# Gate_Driver_3.net
KiCad netlist of a schematic drawn in Altium Designer
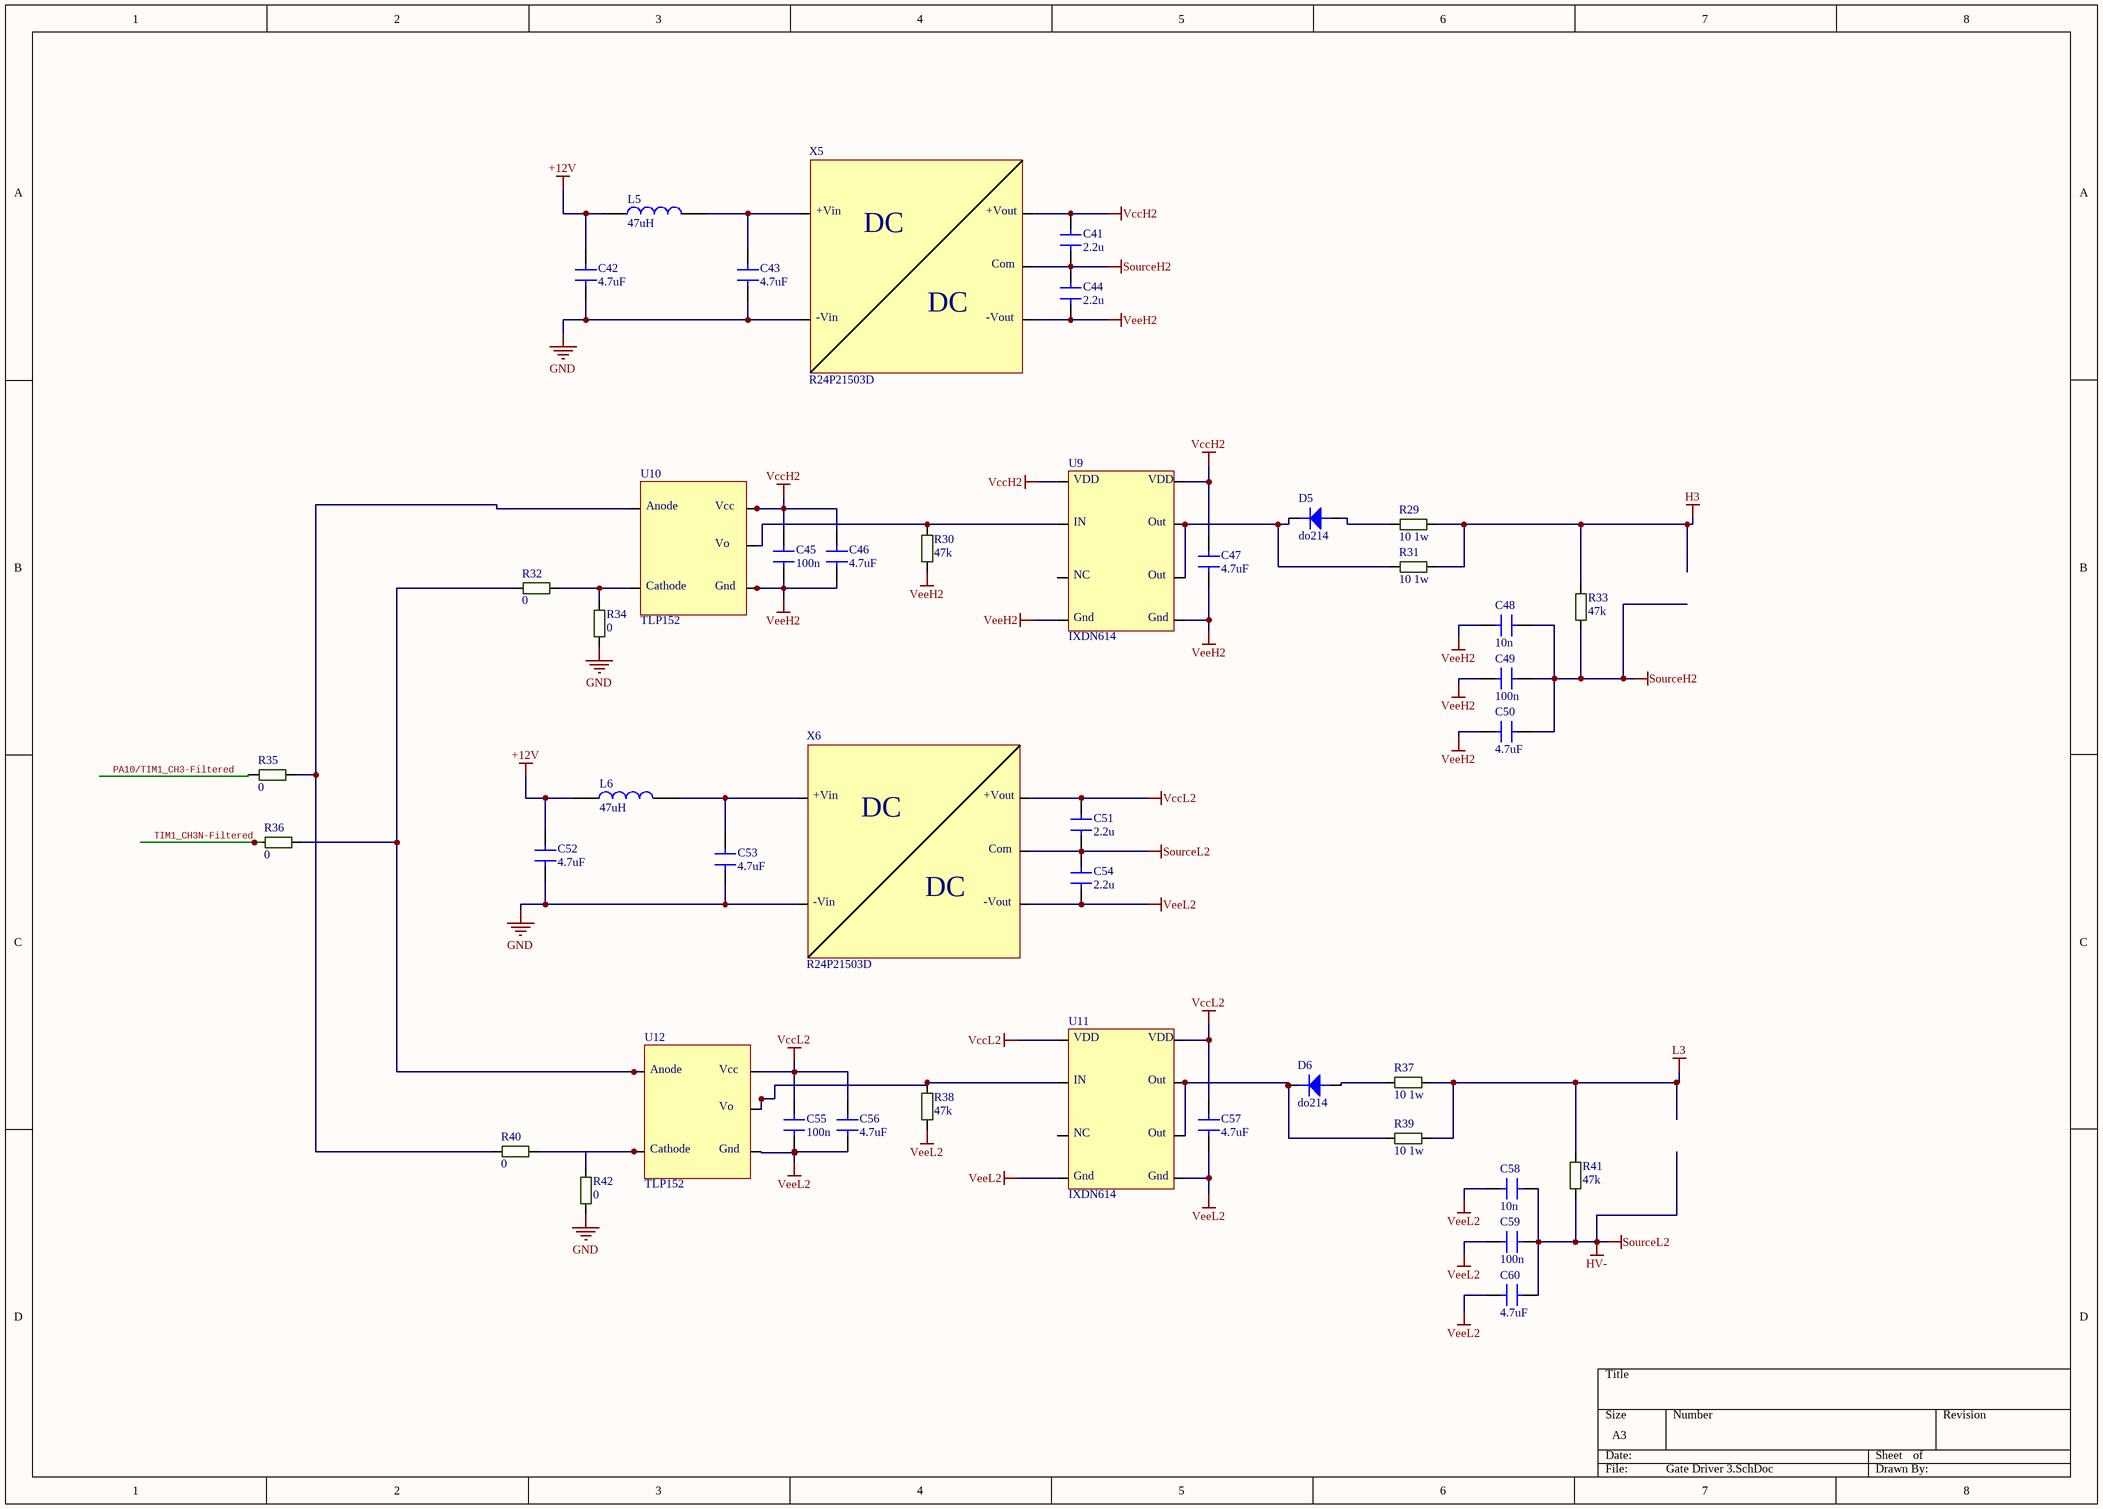
[diagram p0: Gate Driver 3.SchDoc]

(export (version "E")
  (design (tool "Eeschema 10.0.6"))
  (components
    (comp (ref "C41")
      (value "2.2u")
      (footprint "C-0805")
      (libsource (lib "Gate Driver Board") (part "C-0805"))
    )
    (comp (ref "C42")
      (value "4.7uF")
      (footprint "C-1206")
      (description "Cap1206 4.7uF")
      (fields (field (name "ÖZDISAN PART NUMBER") "CL31B475KBHNNNE") (field (name "MANUFACTURER") "SAMSUNG"))
      (libsource (lib "Gate Driver Board") (part "Cap1206"))
    )
    (comp (ref "C43")
      (value "4.7uF")
      (footprint "C-1206")
      (description "Cap1206 4.7uF")
      (fields (field (name "ÖZDISAN PART NUMBER") "CL31B475KBHNNNE") (field (name "MANUFACTURER") "SAMSUNG"))
      (libsource (lib "Gate Driver Board") (part "Cap1206"))
    )
    (comp (ref "C44")
      (value "2.2u")
      (footprint "C-0805")
      (libsource (lib "Gate Driver Board") (part "C-0805"))
    )
    (comp (ref "C45")
      (value "100n")
      (footprint "C-0805")
      (libsource (lib "Gate Driver Board") (part "C-0805"))
    )
    (comp (ref "C46")
      (value "4.7uF")
      (footprint "C-1206")
      (description "Cap1206 4.7uF")
      (libsource (lib "Gate Driver Board") (part "C-1206"))
    )
    (comp (ref "C47")
      (value "4.7uF")
      (footprint "C-1206")
      (description "Cap1206 4.7uF")
      (libsource (lib "Gate Driver Board") (part "C-1206"))
    )
    (comp (ref "C48")
      (value "10n")
      (footprint "C-0805")
      (libsource (lib "Gate Driver Board") (part "C-0805"))
    )
    (comp (ref "C49")
      (value "100n")
      (footprint "C-0805")
      (libsource (lib "Gate Driver Board") (part "C-0805"))
    )
    (comp (ref "C50")
      (value "4.7uF")
      (footprint "C-1206")
      (description "Cap1206 4.7uF")
      (fields (field (name "ÖZDISAN PART NUMBER") " CL31B475KBHNNNE") (field (name "MANUFACTURER") "SAMSUNG"))
      (libsource (lib "Gate Driver Board") (part "Cap1206"))
    )
    (comp (ref "C51")
      (value "2.2u")
      (footprint "C-0805")
      (libsource (lib "Gate Driver Board") (part "C-0805"))
    )
    (comp (ref "C52")
      (value "4.7uF")
      (footprint "C-1206")
      (description "Cap1206 4.7uF")
      (fields (field (name "ÖZDISAN PART NUMBER") "CL31B475KBHNNNE") (field (name "MANUFACTURER") "SAMSUNG"))
      (libsource (lib "Gate Driver Board") (part "Cap1206"))
    )
    (comp (ref "C53")
      (value "4.7uF")
      (footprint "C-1206")
      (description "Cap1206 4.7uF")
      (fields (field (name "ÖZDISAN PART NUMBER") " CL31B475KBHNNNE") (field (name "MANUFACTURER") "SAMSUNG"))
      (libsource (lib "Gate Driver Board") (part "Cap1206"))
    )
    (comp (ref "C54")
      (value "2.2u")
      (footprint "C-0805")
      (libsource (lib "Gate Driver Board") (part "C-0805"))
    )
    (comp (ref "C55")
      (value "100n")
      (footprint "C-0805")
      (libsource (lib "Gate Driver Board") (part "C-0805"))
    )
    (comp (ref "C56")
      (value "4.7uF")
      (footprint "C-1206")
      (description "Cap1206 4.7uF")
      (libsource (lib "Gate Driver Board") (part "C-1206"))
    )
    (comp (ref "C57")
      (value "4.7uF")
      (footprint "C-1206")
      (description "Cap1206 4.7uF")
      (libsource (lib "Gate Driver Board") (part "C-1206"))
    )
    (comp (ref "C58")
      (value "10n")
      (footprint "C-0805")
      (libsource (lib "Gate Driver Board") (part "C-0805"))
    )
    (comp (ref "C59")
      (value "100n")
      (footprint "C-0805")
      (libsource (lib "Gate Driver Board") (part "C-0805"))
    )
    (comp (ref "C60")
      (value "4.7uF")
      (footprint "C-1206")
      (description "Cap1206 4.7uF")
      (fields (field (name "ÖZDISAN PART NUMBER") "CL31B475KBHNNNE") (field (name "MANUFACTURER") "SAMSUNG"))
      (libsource (lib "Gate Driver Board") (part "Cap1206"))
    )
    (comp (ref "D5")
      (value "do214")
      (footprint "DO-214AC")
      (description "DIODE FAST SWITCHING Single 150mA 75V SMT SOD323")
      (libsource (lib "Gate Driver Board") (part "do214"))
    )
    (comp (ref "D6")
      (value "do214")
      (footprint "DO-214AC")
      (description "DIODE FAST SWITCHING Single 150mA 75V SMT SOD323")
      (libsource (lib "Gate Driver Board") (part "do214"))
    )
    (comp (ref "L5")
      (value "47uH")
      (footprint "WE-TPC_282892")
      (libsource (lib "Gate Driver Board") (part "inductor"))
    )
    (comp (ref "L6")
      (value "47uH")
      (footprint "WE-TPC_282892")
      (libsource (lib "Gate Driver Board") (part "inductor"))
    )
    (comp (ref "R29")
      (value "10 1w")
      (footprint "R-2512")
      (libsource (lib "Gate Driver Board") (part "R-2512"))
    )
    (comp (ref "R30")
      (value "47k")
      (footprint "R-0805")
      (description "RES.(2012) 0805 47K Ohms 5% 1/8W-S 100PPM")
      (fields (field (name "MANUFACTURER") "ROYALOHM") (field (name "ÖZDISAN PART NUMBER") "0805S8J0473T5E"))
      (libsource (lib "Gate Driver Board") (part "Res0805"))
    )
    (comp (ref "R31")
      (value "10 1w")
      (footprint "R-2512")
      (libsource (lib "Gate Driver Board") (part "R-2512"))
    )
    (comp (ref "R32")
      (value "0")
      (footprint "R-0805")
      (description "Res0805 0R")
      (fields (field (name "MANUFACTURER") "ROYALOHM") (field (name "ÖZDISAN PART NUMBER") "0805S8J0000T5E"))
      (libsource (lib "Gate Driver Board") (part "Res0805"))
    )
    (comp (ref "R33")
      (value "47k")
      (footprint "R-0805")
      (description "RES.(2012) 0805 47K Ohms 5% 1/8W-S 100PPM")
      (fields (field (name "ÖZDISAN PART NUMBER") "0805S8J0473T5E") (field (name "MANUFACTURER") "ROYALOHM"))
      (libsource (lib "Gate Driver Board") (part "Res0805"))
    )
    (comp (ref "R34")
      (value "0")
      (footprint "R-0805")
      (description "Res0805 0R")
      (fields (field (name "MANUFACTURER") "ROYALOHM") (field (name "ÖZDISAN PART NUMBER") "0805S8J0000T5E"))
      (libsource (lib "Gate Driver Board") (part "Res0805"))
    )
    (comp (ref "R35")
      (value "0")
      (footprint "R-0805")
      (description "Res0805 0R")
      (fields (field (name "MANUFACTURER") "ROYALOHM") (field (name "ÖZDISAN PART NUMBER") "0805S8J0000T5E"))
      (libsource (lib "Gate Driver Board") (part "Res0805"))
    )
    (comp (ref "R36")
      (value "0")
      (footprint "R-0805")
      (description "Res0805 0R")
      (fields (field (name "MANUFACTURER") "ROYALOHM") (field (name "ÖZDISAN PART NUMBER") "0805S8J0000T5E"))
      (libsource (lib "Gate Driver Board") (part "Res0805"))
    )
    (comp (ref "R37")
      (value "10 1w")
      (footprint "R-2512")
      (libsource (lib "Gate Driver Board") (part "R-2512"))
    )
    (comp (ref "R38")
      (value "47k")
      (footprint "R-0805")
      (description "RES.(2012) 0805 47K Ohms 5% 1/8W-S 100PPM")
      (fields (field (name "ÖZDISAN PART NUMBER") "0805S8J0473T5E") (field (name "MANUFACTURER") "ROYALOHM"))
      (libsource (lib "Gate Driver Board") (part "Res0805"))
    )
    (comp (ref "R39")
      (value "10 1w")
      (footprint "R-2512")
      (libsource (lib "Gate Driver Board") (part "R-2512"))
    )
    (comp (ref "R40")
      (value "0")
      (footprint "R-0805")
      (description "Res0805 0R")
      (fields (field (name "MANUFACTURER") "ROYALOHM") (field (name "ÖZDISAN PART NUMBER") "0805S8J0000T5E"))
      (libsource (lib "Gate Driver Board") (part "Res0805"))
    )
    (comp (ref "R41")
      (value "47k")
      (footprint "R-0805")
      (description "RES.(2012) 0805 47K Ohms 5% 1/8W-S 100PPM")
      (fields (field (name "ÖZDISAN PART NUMBER") "0805S8J0473T5E") (field (name "MANUFACTURER") "ROYALOHM"))
      (libsource (lib "Gate Driver Board") (part "Res0805"))
    )
    (comp (ref "R42")
      (value "0")
      (footprint "R-0805")
      (description "Res0805 0R")
      (fields (field (name "MANUFACTURER") "ROYALOHM") (field (name "ÖZDISAN PART NUMBER") "0805S8J0000T5E"))
      (libsource (lib "Gate Driver Board") (part "Res0805"))
    )
    (comp (ref "U9")
      (value "IXDN614")
      (footprint "FAN3122 Soic8")
      (description "14A 8SOIC EXP MTL NON INVERTING")
      (fields
        (field (name "MANUFACTURER") "Ixys Clare")
        (field (name "MANUFACTURER PART NUMBER") "IXDN614SITR")
      )
      (libsource (lib "Gate Driver Board") (part "IXDN614SITR"))
    )
    (comp (ref "U10")
      (value "TLP152")
      (footprint "TLP152")
      (description "OPTOISO 3.75KV GATE DRIVER 6SO-5")
      (fields
        (field (name "MANUFACTURER") "Toshiba")
        (field (name "MANUFACTURER PART NUMBER") "TLP152(TPL,E")
      )
      (libsource (lib "Gate Driver Board") (part "TLP152(TPL,E"))
    )
    (comp (ref "U11")
      (value "IXDN614")
      (footprint "FAN3122 Soic8")
      (description "14A 8SOIC EXP MTL NON INVERTING")
      (fields
        (field (name "MANUFACTURER") "Ixys Clare")
        (field (name "MANUFACTURER PART NUMBER") "IXDN614SITR")
      )
      (libsource (lib "Gate Driver Board") (part "IXDN614SITR"))
    )
    (comp (ref "U12")
      (value "TLP152")
      (footprint "TLP152")
      (description "OPTOISO 3.75KV GATE DRIVER 6SO-5")
      (fields
        (field (name "MANUFACTURER") "Toshiba")
        (field (name "MANUFACTURER PART NUMBER") "TLP152(TPL,E")
      )
      (libsource (lib "Gate Driver Board") (part "TLP152(TPL,E"))
    )
    (comp (ref "X5")
      (value "R24P21503D")
      (footprint "SIP7")
      (fields (field (name "MANUFACTURER") "Recom"))
      (libsource (lib "Gate Driver Board") (part "R24P21503D"))
    )
    (comp (ref "X6")
      (value "R24P21503D")
      (footprint "SIP7")
      (fields (field (name "MANUFACTURER") "Recom"))
      (libsource (lib "Gate Driver Board") (part "R24P21503D"))
    )
  )
  (nets
    (net (code "1") (name "+12V") (class "Default")
      (node (ref "C42") (pin "2") (pinfunction "2_2") (pintype "passive"))
      (node (ref "C52") (pin "2") (pinfunction "2_2") (pintype "passive"))
      (node (ref "L5") (pin "1") (pinfunction "1_1") (pintype "passive"))
      (node (ref "L6") (pin "1") (pinfunction "1_1") (pintype "passive"))
    )
    (net (code "2") (name "/PA10{slash}TIM1_CH3-Filtered") (class "Default")
      (node (ref "R35") (pin "1") (pinfunction "1_1") (pintype "passive"))
    )
    (net (code "3") (name "/TIM1_CH3N-Filtered") (class "Default")
      (node (ref "R36") (pin "1") (pinfunction "1_1") (pintype "passive"))
    )
    (net (code "4") (name "GND") (class "Default")
      (node (ref "C42") (pin "1") (pinfunction "1_1") (pintype "passive"))
      (node (ref "C43") (pin "1") (pinfunction "1_1") (pintype "passive"))
      (node (ref "C52") (pin "1") (pinfunction "1_1") (pintype "passive"))
      (node (ref "C53") (pin "1") (pinfunction "1_1") (pintype "passive"))
      (node (ref "R34") (pin "1") (pinfunction "1_1") (pintype "passive"))
      (node (ref "R42") (pin "1") (pinfunction "1_1") (pintype "passive"))
      (node (ref "X5") (pin "2") (pinfunction "2_2") (pintype "passive"))
      (node (ref "X6") (pin "2") (pinfunction "2_2") (pintype "passive"))
    )
    (net (code "5") (name "H3") (class "Default")
      (node (ref "R29") (pin "2") (pinfunction "2_2") (pintype "passive"))
      (node (ref "R31") (pin "2") (pinfunction "2_2") (pintype "passive"))
      (node (ref "R33") (pin "2") (pinfunction "2_2") (pintype "passive"))
    )
    (net (code "6") (name "HV-") (class "Default")
      (node (ref "C51") (pin "1") (pinfunction "1_1") (pintype "passive"))
      (node (ref "C54") (pin "2") (pinfunction "2_2") (pintype "passive"))
      (node (ref "C58") (pin "1") (pinfunction "1_1") (pintype "passive"))
      (node (ref "C59") (pin "1") (pinfunction "1_1") (pintype "passive"))
      (node (ref "C60") (pin "2") (pinfunction "2_2") (pintype "passive"))
      (node (ref "R41") (pin "1") (pinfunction "1_1") (pintype "passive"))
      (node (ref "X6") (pin "6") (pinfunction "6_6") (pintype "passive"))
    )
    (net (code "7") (name "L3") (class "Default")
      (node (ref "R37") (pin "2") (pinfunction "2_2") (pintype "passive"))
      (node (ref "R39") (pin "2") (pinfunction "2_2") (pintype "passive"))
      (node (ref "R41") (pin "2") (pinfunction "2_2") (pintype "passive"))
    )
    (net (code "8") (name "Net-(C43-Pad2)") (class "Default")
      (node (ref "C43") (pin "2") (pinfunction "2_2") (pintype "passive"))
      (node (ref "L5") (pin "2") (pinfunction "2_2") (pintype "passive"))
      (node (ref "X5") (pin "1") (pinfunction "1_1") (pintype "passive"))
    )
    (net (code "9") (name "Net-(C53-Pad2)") (class "Default")
      (node (ref "C53") (pin "2") (pinfunction "2_2") (pintype "passive"))
      (node (ref "L6") (pin "2") (pinfunction "2_2") (pintype "passive"))
      (node (ref "X6") (pin "1") (pinfunction "1_1") (pintype "passive"))
    )
    (net (code "10") (name "Net-(D5-Pada)") (class "Default")
      (node (ref "D5") (pin "a") (pinfunction "a_a") (pintype "passive"))
      (node (ref "R29") (pin "1") (pinfunction "1_1") (pintype "passive"))
    )
    (net (code "11") (name "Net-(D5-Padk)") (class "Default")
      (node (ref "D5") (pin "k") (pinfunction "k_k") (pintype "passive"))
      (node (ref "R31") (pin "1") (pinfunction "1_1") (pintype "passive"))
      (node (ref "U9") (pin "6") (pinfunction "6_6") (pintype "passive"))
      (node (ref "U9") (pin "7") (pinfunction "7_7") (pintype "passive"))
    )
    (net (code "12") (name "Net-(D6-Pada)") (class "Default")
      (node (ref "D6") (pin "a") (pinfunction "a_a") (pintype "passive"))
      (node (ref "R37") (pin "1") (pinfunction "1_1") (pintype "passive"))
    )
    (net (code "13") (name "Net-(D6-Padk)") (class "Default")
      (node (ref "D6") (pin "k") (pinfunction "k_k") (pintype "passive"))
      (node (ref "R39") (pin "1") (pinfunction "1_1") (pintype "passive"))
      (node (ref "U11") (pin "6") (pinfunction "6_6") (pintype "passive"))
      (node (ref "U11") (pin "7") (pinfunction "7_7") (pintype "passive"))
    )
    (net (code "14") (name "Net-(R30-Pad2)") (class "Default")
      (node (ref "R30") (pin "2") (pinfunction "2_2") (pintype "passive"))
      (node (ref "U10") (pin "4") (pinfunction "4_4") (pintype "passive"))
      (node (ref "U9") (pin "2") (pinfunction "2_2") (pintype "passive"))
    )
    (net (code "15") (name "Net-(R32-Pad1)") (class "Default")
      (node (ref "R32") (pin "1") (pinfunction "1_1") (pintype "passive"))
      (node (ref "R36") (pin "2") (pinfunction "2_2") (pintype "passive"))
      (node (ref "U12") (pin "1") (pinfunction "1_1") (pintype "passive"))
    )
    (net (code "16") (name "Net-(R32-Pad2)") (class "Default")
      (node (ref "R32") (pin "2") (pinfunction "2_2") (pintype "passive"))
      (node (ref "R34") (pin "2") (pinfunction "2_2") (pintype "passive"))
      (node (ref "U10") (pin "2") (pinfunction "2_2") (pintype "passive"))
    )
    (net (code "17") (name "Net-(R35-Pad2)") (class "Default")
      (node (ref "R35") (pin "2") (pinfunction "2_2") (pintype "passive"))
      (node (ref "R40") (pin "1") (pinfunction "1_1") (pintype "passive"))
      (node (ref "U10") (pin "1") (pinfunction "1_1") (pintype "passive"))
    )
    (net (code "18") (name "Net-(R38-Pad2)") (class "Default")
      (node (ref "R38") (pin "2") (pinfunction "2_2") (pintype "passive"))
      (node (ref "U11") (pin "2") (pinfunction "2_2") (pintype "passive"))
      (node (ref "U12") (pin "4") (pinfunction "4_4") (pintype "passive"))
    )
    (net (code "19") (name "Net-(R40-Pad2)") (class "Default")
      (node (ref "R40") (pin "2") (pinfunction "2_2") (pintype "passive"))
      (node (ref "R42") (pin "2") (pinfunction "2_2") (pintype "passive"))
      (node (ref "U12") (pin "2") (pinfunction "2_2") (pintype "passive"))
    )
    (net (code "20") (name "SourceH2") (class "Default")
      (node (ref "C41") (pin "1") (pinfunction "1_1") (pintype "passive"))
      (node (ref "C44") (pin "2") (pinfunction "2_2") (pintype "passive"))
      (node (ref "C48") (pin "1") (pinfunction "1_1") (pintype "passive"))
      (node (ref "C49") (pin "1") (pinfunction "1_1") (pintype "passive"))
      (node (ref "C50") (pin "2") (pinfunction "2_2") (pintype "passive"))
      (node (ref "R33") (pin "1") (pinfunction "1_1") (pintype "passive"))
      (node (ref "X5") (pin "6") (pinfunction "6_6") (pintype "passive"))
    )
    (net (code "21") (name "VccH2") (class "Default")
      (node (ref "C41") (pin "2") (pinfunction "2_2") (pintype "passive"))
      (node (ref "C45") (pin "2") (pinfunction "2_2") (pintype "passive"))
      (node (ref "C46") (pin "2") (pinfunction "2_2") (pintype "passive"))
      (node (ref "C47") (pin "2") (pinfunction "2_2") (pintype "passive"))
      (node (ref "U10") (pin "5") (pinfunction "5_5") (pintype "passive"))
      (node (ref "U9") (pin "1") (pinfunction "1_1") (pintype "passive"))
      (node (ref "U9") (pin "8") (pinfunction "8_8") (pintype "passive"))
      (node (ref "X5") (pin "7") (pinfunction "7_7") (pintype "passive"))
    )
    (net (code "22") (name "VccL2") (class "Default")
      (node (ref "C51") (pin "2") (pinfunction "2_2") (pintype "passive"))
      (node (ref "C55") (pin "2") (pinfunction "2_2") (pintype "passive"))
      (node (ref "C56") (pin "2") (pinfunction "2_2") (pintype "passive"))
      (node (ref "C57") (pin "2") (pinfunction "2_2") (pintype "passive"))
      (node (ref "U11") (pin "1") (pinfunction "1_1") (pintype "passive"))
      (node (ref "U11") (pin "8") (pinfunction "8_8") (pintype "passive"))
      (node (ref "U12") (pin "5") (pinfunction "5_5") (pintype "passive"))
      (node (ref "X6") (pin "7") (pinfunction "7_7") (pintype "passive"))
    )
    (net (code "23") (name "VeeH2") (class "Default")
      (node (ref "C44") (pin "1") (pinfunction "1_1") (pintype "passive"))
      (node (ref "C45") (pin "1") (pinfunction "1_1") (pintype "passive"))
      (node (ref "C46") (pin "1") (pinfunction "1_1") (pintype "passive"))
      (node (ref "C47") (pin "1") (pinfunction "1_1") (pintype "passive"))
      (node (ref "C48") (pin "2") (pinfunction "2_2") (pintype "passive"))
      (node (ref "C49") (pin "2") (pinfunction "2_2") (pintype "passive"))
      (node (ref "C50") (pin "1") (pinfunction "1_1") (pintype "passive"))
      (node (ref "R30") (pin "1") (pinfunction "1_1") (pintype "passive"))
      (node (ref "U10") (pin "3") (pinfunction "3_3") (pintype "passive"))
      (node (ref "U9") (pin "4") (pinfunction "4_4") (pintype "passive"))
      (node (ref "U9") (pin "5") (pinfunction "5_5") (pintype "passive"))
      (node (ref "X5") (pin "5") (pinfunction "5_5") (pintype "passive"))
    )
    (net (code "24") (name "VeeL2") (class "Default")
      (node (ref "C54") (pin "1") (pinfunction "1_1") (pintype "passive"))
      (node (ref "C55") (pin "1") (pinfunction "1_1") (pintype "passive"))
      (node (ref "C56") (pin "1") (pinfunction "1_1") (pintype "passive"))
      (node (ref "C57") (pin "1") (pinfunction "1_1") (pintype "passive"))
      (node (ref "C58") (pin "2") (pinfunction "2_2") (pintype "passive"))
      (node (ref "C59") (pin "2") (pinfunction "2_2") (pintype "passive"))
      (node (ref "C60") (pin "1") (pinfunction "1_1") (pintype "passive"))
      (node (ref "R38") (pin "1") (pinfunction "1_1") (pintype "passive"))
      (node (ref "U11") (pin "4") (pinfunction "4_4") (pintype "passive"))
      (node (ref "U11") (pin "5") (pinfunction "5_5") (pintype "passive"))
      (node (ref "U12") (pin "3") (pinfunction "3_3") (pintype "passive"))
      (node (ref "X6") (pin "5") (pinfunction "5_5") (pintype "passive"))
    )
    (net (code "25") (name "unconnected-(U9-Pad3)") (class "Default")
      (node (ref "U9") (pin "3") (pinfunction "3_3") (pintype "passive"))
    )
    (net (code "26") (name "unconnected-(U11-Pad3)") (class "Default")
      (node (ref "U11") (pin "3") (pinfunction "3_3") (pintype "passive"))
    )
  )
)
